# spa_psu.net
KiCad netlist of a schematic drawn in Altium Designer
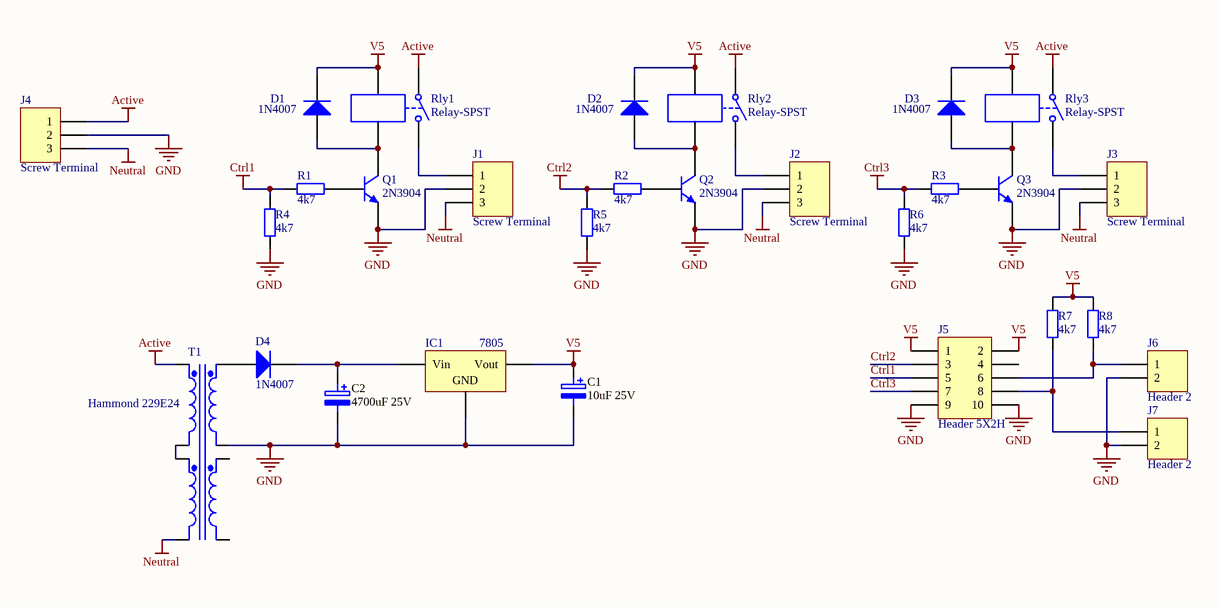
[diagram p0: spa_psu.SchDoc]

(export (version "E")
  (design (tool "Eeschema 10.0.6"))
  (components
    (comp (ref "C1")
      (value "10uF 25V")
      (footprint "RAD-0.2")
      (description "Electrolytic Capacitor")
      (libsource (lib "umbilical_interface_1") (part "ELECTRO2"))
    )
    (comp (ref "C2")
      (value "4700uF 25V")
      (footprint "cap_radial_600")
      (description "Electrolytic Capacitor")
      (libsource (lib "umbilical_interface_1") (part "ELECTRO2"))
    )
    (comp (ref "D1")
      (value "1N4007")
      (footprint "DO-41")
      (description "1 Amp General Purpose Rectifier")
      (fields (field (name "PUBLISHER") "Altium Limited"))
      (libsource (lib "Miscellaneous Devices") (part "Diode 1N4007"))
    )
    (comp (ref "D2")
      (value "1N4007")
      (footprint "DO-41")
      (description "1 Amp General Purpose Rectifier")
      (fields (field (name "PUBLISHER") "Altium Limited"))
      (libsource (lib "Miscellaneous Devices") (part "Diode 1N4007"))
    )
    (comp (ref "D3")
      (value "1N4007")
      (footprint "DO-41")
      (description "1 Amp General Purpose Rectifier")
      (fields (field (name "PUBLISHER") "Altium Limited"))
      (libsource (lib "Miscellaneous Devices") (part "Diode 1N4007"))
    )
    (comp (ref "D4")
      (value "1N4007")
      (footprint "DO-41")
      (description "1 Amp General Purpose Rectifier")
      (fields (field (name "PUBLISHER") "Altium Limited"))
      (libsource (lib "Miscellaneous Devices") (part "Diode 1N4007"))
    )
    (comp (ref "IC1")
      (value "7805")
      (footprint "TO-220-AB")
      (description "Voltage Regulator")
      (fields (field (name "PUBLISHER") "Altium Limited"))
      (libsource (lib "Miscellaneous Devices") (part "Volt Reg"))
    )
    (comp (ref "J1")
      (value "Screw Terminal")
      (footprint "Screw_Terminal_3way")
      (description "Header, 3-Pin")
      (fields (field (name "PUBLISHER") "Altium Limited"))
      (libsource (lib "") (part "Header 3_1"))
    )
    (comp (ref "J2")
      (value "Screw Terminal")
      (footprint "Screw_Terminal_3way")
      (description "Header, 3-Pin")
      (fields (field (name "PUBLISHER") "Altium Limited"))
      (libsource (lib "") (part "Header 3_1"))
    )
    (comp (ref "J3")
      (value "Screw Terminal")
      (footprint "Screw_Terminal_3way")
      (description "Header, 3-Pin")
      (fields (field (name "PUBLISHER") "Altium Limited"))
      (libsource (lib "") (part "Header 3_1"))
    )
    (comp (ref "J4")
      (value "Screw Terminal")
      (footprint "Screw_Terminal_3way")
      (description "Header, 3-Pin")
      (fields (field (name "PUBLISHER") "Altium Limited"))
      (libsource (lib "Miscellaneous Connectors") (part "Header 3"))
    )
    (comp (ref "J5")
      (value "Header 5X2H")
      (footprint "HDR2X5H")
      (description "Header, 5-Pin, Dual row, Right Angle")
      (fields (field (name "PUBLISHER") "Altium Limited"))
      (libsource (lib "Miscellaneous Connectors") (part "Header 5X2H"))
    )
    (comp (ref "J6")
      (value "Header 2")
      (footprint "HDR1X2_WIDE")
      (description "Header, 2-Pin")
      (fields (field (name "PUBLISHER") "Altium Limited"))
      (libsource (lib "Miscellaneous Connectors") (part "Header 2"))
    )
    (comp (ref "J7")
      (value "Header 2")
      (footprint "HDR1X2_WIDE")
      (description "Header, 2-Pin")
      (fields (field (name "PUBLISHER") "Altium Limited"))
      (libsource (lib "Miscellaneous Connectors") (part "Header 2"))
    )
    (comp (ref "Q1")
      (value "2N3904")
      (footprint "TO-92A")
      (description "NPN General Purpose Amplifier")
      (fields (field (name "PUBLISHER") "Altium Limited"))
      (libsource (lib "Miscellaneous Devices") (part "2N3904"))
    )
    (comp (ref "Q2")
      (value "2N3904")
      (footprint "TO-92A")
      (description "NPN General Purpose Amplifier")
      (fields (field (name "PUBLISHER") "Altium Limited"))
      (libsource (lib "Miscellaneous Devices") (part "2N3904"))
    )
    (comp (ref "Q3")
      (value "2N3904")
      (footprint "TO-92A")
      (description "NPN General Purpose Amplifier")
      (fields (field (name "PUBLISHER") "Altium Limited"))
      (libsource (lib "Miscellaneous Devices") (part "2N3904"))
    )
    (comp (ref "R1")
      (value "4k7")
      (footprint "AXIAL-0.4")
      (description "Resistor")
      (fields (field (name "PUBLISHER") "Altium Limited"))
      (libsource (lib "") (part "Res2_1"))
    )
    (comp (ref "R2")
      (value "4k7")
      (footprint "AXIAL-0.4")
      (description "Resistor")
      (fields (field (name "PUBLISHER") "Altium Limited"))
      (libsource (lib "") (part "Res2_1"))
    )
    (comp (ref "R3")
      (value "4k7")
      (footprint "AXIAL-0.4")
      (description "Resistor")
      (fields (field (name "PUBLISHER") "Altium Limited"))
      (libsource (lib "") (part "Res2_1"))
    )
    (comp (ref "R4")
      (value "4k7")
      (footprint "AXIAL-0.4")
      (description "Resistor")
      (fields (field (name "PUBLISHER") "Altium Limited"))
      (libsource (lib "Miscellaneous Devices") (part "Res2"))
    )
    (comp (ref "R5")
      (value "4k7")
      (footprint "AXIAL-0.4")
      (description "Resistor")
      (fields (field (name "PUBLISHER") "Altium Limited"))
      (libsource (lib "Miscellaneous Devices") (part "Res2"))
    )
    (comp (ref "R6")
      (value "4k7")
      (footprint "AXIAL-0.4")
      (description "Resistor")
      (fields (field (name "PUBLISHER") "Altium Limited"))
      (libsource (lib "Miscellaneous Devices") (part "Res2"))
    )
    (comp (ref "R7")
      (value "4k7")
      (footprint "AXIAL-0.4")
      (description "Resistor")
      (fields (field (name "PUBLISHER") "Altium Limited"))
      (libsource (lib "Miscellaneous Devices") (part "Res2"))
    )
    (comp (ref "R8")
      (value "4k7")
      (footprint "AXIAL-0.4")
      (description "Resistor")
      (fields (field (name "PUBLISHER") "Altium Limited"))
      (libsource (lib "Miscellaneous Devices") (part "Res2"))
    )
    (comp (ref "Rly1")
      (value "Relay-SPST")
      (footprint "Relay_8A")
      (description "Single-Pole Single-Throw Relay")
      (fields (field (name "PUBLISHER") "Altium Limited"))
      (libsource (lib "Miscellaneous Devices") (part "Relay-SPST"))
    )
    (comp (ref "Rly2")
      (value "Relay-SPST")
      (footprint "Relay_8A")
      (description "Single-Pole Single-Throw Relay")
      (fields (field (name "PUBLISHER") "Altium Limited"))
      (libsource (lib "Miscellaneous Devices") (part "Relay-SPST"))
    )
    (comp (ref "Rly3")
      (value "Relay-SPST")
      (footprint "Relay_8A")
      (description "Single-Pole Single-Throw Relay")
      (fields (field (name "PUBLISHER") "Altium Limited"))
      (libsource (lib "Miscellaneous Devices") (part "Relay-SPST"))
    )
    (comp (ref "T1")
      (value "Hammond 229E24")
      (footprint "229E24")
      (description "Buck-boost Transformer (Ideal)")
      (fields (field (name "PUBLISHER") "Altium Limited"))
      (libsource (lib "Miscellaneous Devices") (part "Trans BB"))
    )
  )
  (nets
    (net (code "1") (name "Active") (class "Default")
      (node (ref "J4") (pin "1") (pinfunction "1_1") (pintype "passive"))
      (node (ref "Rly1") (pin "1") (pinfunction "1_1") (pintype "passive"))
      (node (ref "Rly2") (pin "1") (pinfunction "1_1") (pintype "passive"))
      (node (ref "Rly3") (pin "1") (pinfunction "1_1") (pintype "passive"))
      (node (ref "T1") (pin "1") (pinfunction "Pri1+_1") (pintype "passive"))
    )
    (net (code "2") (name "Ctrl1") (class "Default")
      (node (ref "J5") (pin "5") (pinfunction "5_5") (pintype "passive"))
      (node (ref "R1") (pin "1") (pinfunction "1_1") (pintype "passive"))
      (node (ref "R4") (pin "2") (pinfunction "2_2") (pintype "passive"))
    )
    (net (code "3") (name "Ctrl2") (class "Default")
      (node (ref "J5") (pin "3") (pinfunction "3_3") (pintype "passive"))
      (node (ref "R2") (pin "1") (pinfunction "1_1") (pintype "passive"))
      (node (ref "R5") (pin "2") (pinfunction "2_2") (pintype "passive"))
    )
    (net (code "4") (name "Ctrl3") (class "Default")
      (node (ref "J5") (pin "7") (pinfunction "7_7") (pintype "passive"))
      (node (ref "R3") (pin "1") (pinfunction "1_1") (pintype "passive"))
      (node (ref "R6") (pin "2") (pinfunction "2_2") (pintype "passive"))
    )
    (net (code "5") (name "GND") (class "Default")
      (node (ref "C1") (pin "2") (pinfunction "2_2") (pintype "passive"))
      (node (ref "C2") (pin "2") (pinfunction "2_2") (pintype "passive"))
      (node (ref "IC1") (pin "2") (pinfunction "GND_2") (pintype "passive"))
      (node (ref "J1") (pin "2") (pinfunction "2_2") (pintype "passive"))
      (node (ref "J2") (pin "2") (pinfunction "2_2") (pintype "passive"))
      (node (ref "J3") (pin "2") (pinfunction "2_2") (pintype "passive"))
      (node (ref "J4") (pin "2") (pinfunction "2_2") (pintype "passive"))
      (node (ref "J5") (pin "10") (pinfunction "10_10") (pintype "passive"))
      (node (ref "J5") (pin "9") (pinfunction "9_9") (pintype "passive"))
      (node (ref "J6") (pin "2") (pinfunction "2_2") (pintype "passive"))
      (node (ref "J7") (pin "2") (pinfunction "2_2") (pintype "passive"))
      (node (ref "Q1") (pin "1") (pinfunction "E_1") (pintype "passive"))
      (node (ref "Q2") (pin "1") (pinfunction "E_1") (pintype "passive"))
      (node (ref "Q3") (pin "1") (pinfunction "E_1") (pintype "passive"))
      (node (ref "R4") (pin "1") (pinfunction "1_1") (pintype "passive"))
      (node (ref "R5") (pin "1") (pinfunction "1_1") (pintype "passive"))
      (node (ref "R6") (pin "1") (pinfunction "1_1") (pintype "passive"))
      (node (ref "T1") (pin "6") (pinfunction "Sec1-_6") (pintype "passive"))
    )
    (net (code "6") (name "Net-(D1-A)") (class "Default")
      (node (ref "D1") (pin "1") (pinfunction "A_1") (pintype "passive"))
      (node (ref "Q1") (pin "3") (pinfunction "C_3") (pintype "passive"))
      (node (ref "Rly1") (pin "4") (pinfunction "4_4") (pintype "passive"))
    )
    (net (code "7") (name "Net-(D2-A)") (class "Default")
      (node (ref "D2") (pin "1") (pinfunction "A_1") (pintype "passive"))
      (node (ref "Q2") (pin "3") (pinfunction "C_3") (pintype "passive"))
      (node (ref "Rly2") (pin "4") (pinfunction "4_4") (pintype "passive"))
    )
    (net (code "8") (name "Net-(D3-A)") (class "Default")
      (node (ref "D3") (pin "1") (pinfunction "A_1") (pintype "passive"))
      (node (ref "Q3") (pin "3") (pinfunction "C_3") (pintype "passive"))
      (node (ref "Rly3") (pin "4") (pinfunction "4_4") (pintype "passive"))
    )
    (net (code "9") (name "Net-(D4-A)") (class "Default")
      (node (ref "D4") (pin "1") (pinfunction "A_1") (pintype "passive"))
      (node (ref "T1") (pin "5") (pinfunction "Sec1+_5") (pintype "passive"))
    )
    (net (code "10") (name "Net-(D4-K)") (class "Default")
      (node (ref "C2") (pin "1") (pinfunction "1_1") (pintype "passive"))
      (node (ref "D4") (pin "2") (pinfunction "K_2") (pintype "passive"))
      (node (ref "IC1") (pin "1") (pinfunction "Vin_1") (pintype "passive"))
    )
    (net (code "11") (name "Net-(J1-Pad1)") (class "Default")
      (node (ref "J1") (pin "1") (pinfunction "1_1") (pintype "passive"))
      (node (ref "Rly1") (pin "2") (pinfunction "2_2") (pintype "passive"))
    )
    (net (code "12") (name "Net-(J2-Pad1)") (class "Default")
      (node (ref "J2") (pin "1") (pinfunction "1_1") (pintype "passive"))
      (node (ref "Rly2") (pin "2") (pinfunction "2_2") (pintype "passive"))
    )
    (net (code "13") (name "Net-(J3-Pad1)") (class "Default")
      (node (ref "J3") (pin "1") (pinfunction "1_1") (pintype "passive"))
      (node (ref "Rly3") (pin "2") (pinfunction "2_2") (pintype "passive"))
    )
    (net (code "14") (name "Net-(J5-Pad6)") (class "Default")
      (node (ref "J5") (pin "6") (pinfunction "6_6") (pintype "passive"))
      (node (ref "J6") (pin "1") (pinfunction "1_1") (pintype "passive"))
      (node (ref "R8") (pin "1") (pinfunction "1_1") (pintype "passive"))
    )
    (net (code "15") (name "Net-(J5-Pad8)") (class "Default")
      (node (ref "J5") (pin "8") (pinfunction "8_8") (pintype "passive"))
      (node (ref "J7") (pin "1") (pinfunction "1_1") (pintype "passive"))
      (node (ref "R7") (pin "1") (pinfunction "1_1") (pintype "passive"))
    )
    (net (code "16") (name "Net-(Q1-B)") (class "Default")
      (node (ref "Q1") (pin "2") (pinfunction "B_2") (pintype "passive"))
      (node (ref "R1") (pin "2") (pinfunction "2_2") (pintype "passive"))
    )
    (net (code "17") (name "Net-(Q2-B)") (class "Default")
      (node (ref "Q2") (pin "2") (pinfunction "B_2") (pintype "passive"))
      (node (ref "R2") (pin "2") (pinfunction "2_2") (pintype "passive"))
    )
    (net (code "18") (name "Net-(Q3-B)") (class "Default")
      (node (ref "Q3") (pin "2") (pinfunction "B_2") (pintype "passive"))
      (node (ref "R3") (pin "2") (pinfunction "2_2") (pintype "passive"))
    )
    (net (code "19") (name "Net-(T1-Pri1-)") (class "Default")
      (node (ref "T1") (pin "2") (pinfunction "Pri1-_2") (pintype "passive"))
      (node (ref "T1") (pin "3") (pinfunction "Pri2+_3") (pintype "passive"))
    )
    (net (code "20") (name "Neutral") (class "Default")
      (node (ref "J1") (pin "3") (pinfunction "3_3") (pintype "passive"))
      (node (ref "J2") (pin "3") (pinfunction "3_3") (pintype "passive"))
      (node (ref "J3") (pin "3") (pinfunction "3_3") (pintype "passive"))
      (node (ref "J4") (pin "3") (pinfunction "3_3") (pintype "passive"))
      (node (ref "T1") (pin "4") (pinfunction "Pri2-_4") (pintype "passive"))
    )
    (net (code "21") (name "V5") (class "Default")
      (node (ref "C1") (pin "1") (pinfunction "1_1") (pintype "passive"))
      (node (ref "D1") (pin "2") (pinfunction "K_2") (pintype "passive"))
      (node (ref "D2") (pin "2") (pinfunction "K_2") (pintype "passive"))
      (node (ref "D3") (pin "2") (pinfunction "K_2") (pintype "passive"))
      (node (ref "IC1") (pin "3") (pinfunction "Vout_3") (pintype "passive"))
      (node (ref "J5") (pin "1") (pinfunction "1_1") (pintype "passive"))
      (node (ref "J5") (pin "2") (pinfunction "2_2") (pintype "passive"))
      (node (ref "R7") (pin "2") (pinfunction "2_2") (pintype "passive"))
      (node (ref "R8") (pin "2") (pinfunction "2_2") (pintype "passive"))
      (node (ref "Rly1") (pin "3") (pinfunction "3_3") (pintype "passive"))
      (node (ref "Rly2") (pin "3") (pinfunction "3_3") (pintype "passive"))
      (node (ref "Rly3") (pin "3") (pinfunction "3_3") (pintype "passive"))
    )
    (net (code "22") (name "unconnected-(J5-Pad4)") (class "Default")
      (node (ref "J5") (pin "4") (pinfunction "4_4") (pintype "passive"))
    )
    (net (code "23") (name "unconnected-(T1-Sec2+-Pad7)") (class "Default")
      (node (ref "T1") (pin "7") (pinfunction "Sec2+_7") (pintype "passive"))
    )
    (net (code "24") (name "unconnected-(T1-Sec2--Pad8)") (class "Default")
      (node (ref "T1") (pin "8") (pinfunction "Sec2-_8") (pintype "passive"))
    )
  )
)
